# I2C_Serial_ID_EEPROM.net
KiCad netlist of a schematic drawn in Altium Designer
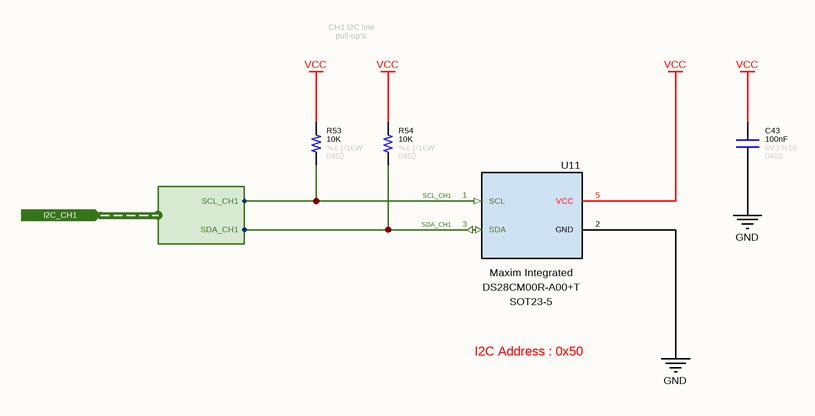
[diagram p0: I2C Serial ID EEPROM.SchDoc]

(export (version "E")
  (design (tool "Eeschema 10.0.6"))
  (components
    (comp (ref "C43")
      (value "100nF")
      (footprint "CAPACITOR_0402")
      (description "Capacitor - 100nF [0402-6V3] (Ceramic)")
      (fields
        (field (name "MANUFACTURER PART NUMBER") "04026D104KAT4A")
        (field (name "TOLERANCE") "%10")
        (field (name "VOLTAGE") "6V3")
        (field (name "CASE") "0402")
        (field (name "Comment") "Capacitor - 100nF [0402] (Ceramic)")
      )
      (libsource (lib "P101DA_Library") (part "Capacitor - 100nF [0402-6V3]"))
    )
    (comp (ref "R53")
      (value "10K")
      (footprint "RESISTOR_0402")
      (description "Thick Film Resistors - SMD 1/16 W 10 KOhm 1%")
      (fields
        (field (name "MANUFACTURER PART NUMBER") "CRCW040210K0FKED")
        (field (name "TOLERANCE") "%1")
        (field (name "CASE") "0402")
        (field (name "POWER") "1/16W")
        (field (name "Comment") "10K - 0402 - %1 - 1/16W")
      )
      (libsource (lib "P101DA_Library") (part "Resistor - 10K [0402]"))
    )
    (comp (ref "R54")
      (value "10K")
      (footprint "RESISTOR_0402")
      (description "Thick Film Resistors - SMD 1/16 W 10 KOhm 1%")
      (fields
        (field (name "MANUFACTURER PART NUMBER") "CRCW040210K0FKED")
        (field (name "TOLERANCE") "%1")
        (field (name "CASE") "0402")
        (field (name "POWER") "1/16W")
        (field (name "Comment") "10K - 0402 - %1 - 1/16W")
      )
      (libsource (lib "P101DA_Library") (part "Resistor - 10K [0402]"))
    )
    (comp (ref "U11")
      (value "DS28CM00R-A00+T")
      (footprint "SOT-23-5")
      (description "Security ICs / Authentication ICs I C/SMBus Silicon Serial Number")
      (fields
        (field (name "MANUFACTURER NAME") "Maxim Integrated")
        (field (name "MANUFACTURER PART NUMBER") "DS28CM00R-A00+T")
        (field (name "CASE") "SOT23-5")
      )
      (libsource (lib "P101DA_Library") (part "IC - DS28C"))
    )
  )
  (nets
    (net (code "2") (name "/SCL_CH1") (class "Default")
      (node (ref "R53") (pin "1") (pinfunction "1_1") (pintype "passive"))
      (node (ref "U11") (pin "1") (pinfunction "SCL_1") (pintype "input"))
    )
    (net (code "3") (name "/SDA_CH1") (class "Default")
      (node (ref "R54") (pin "1") (pinfunction "1_1") (pintype "passive"))
      (node (ref "U11") (pin "3") (pinfunction "SDA_3") (pintype "bidirectional"))
    )
    (net (code "5") (name "GND") (class "Default")
      (node (ref "C43") (pin "1") (pinfunction "1_1") (pintype "passive"))
      (node (ref "U11") (pin "2") (pinfunction "GND_2") (pintype "passive"))
    )
    (net (code "6") (name "VCC") (class "Default")
      (node (ref "C43") (pin "2") (pinfunction "2_2") (pintype "passive"))
      (node (ref "R53") (pin "2") (pinfunction "2_2") (pintype "passive"))
      (node (ref "R54") (pin "2") (pinfunction "2_2") (pintype "passive"))
      (node (ref "U11") (pin "5") (pinfunction "VCC_5") (pintype "power_in"))
    )
    (net (code "7") (name "unconnected-(U11-NC-Pad4)") (class "Default")
      (node (ref "U11") (pin "4") (pinfunction "NC_4") (pintype "passive"))
    )
  )
)
